# DC-DC_5V.net
KiCad netlist of a schematic drawn in EasyEDA Pro
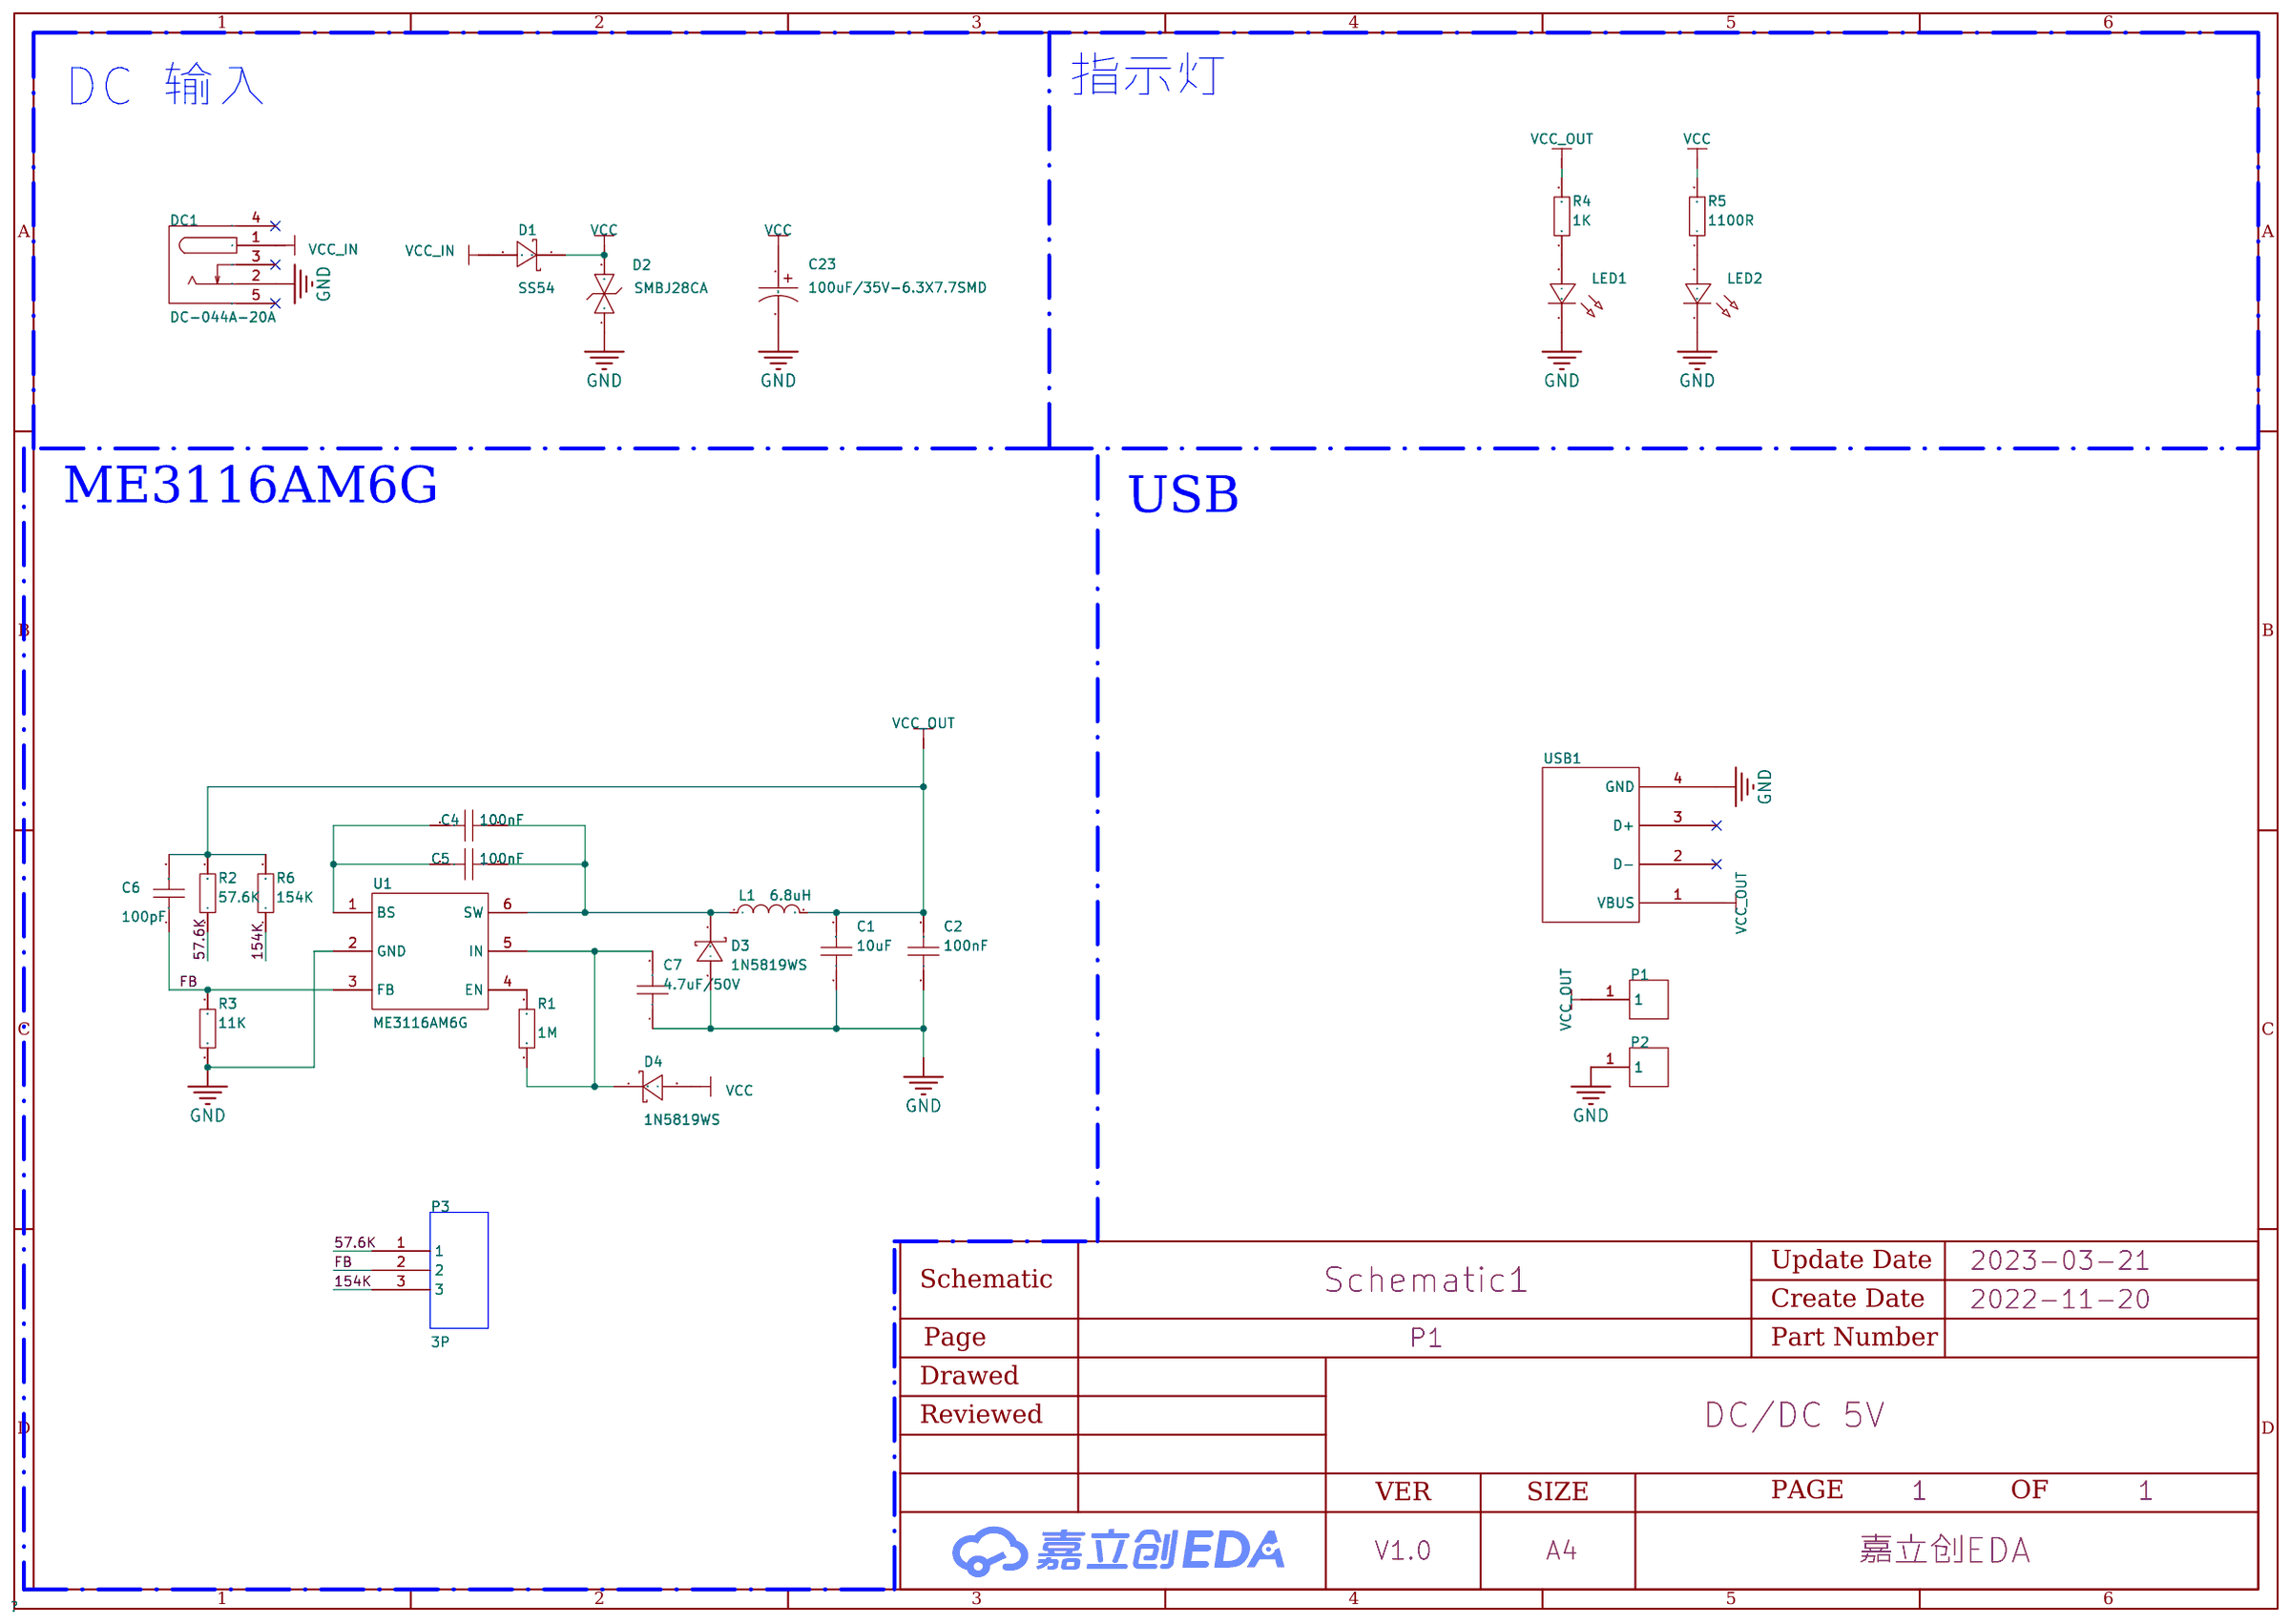
[diagram p0: schematic sheet]

(export (version "E")
  (design (tool "Eeschema 10.0.6"))
  (components
    (comp (ref "C1")
      (value "100nF")
      (footprint "easyedapro:C0603")
      (libsource (lib "easyedapro") (part "C1210X7R475K630NT"))
    )
    (comp (ref "C2")
      (value "100nF")
      (footprint "easyedapro:C0603")
      (libsource (lib "easyedapro") (part "C1210X7R475K630NT"))
    )
    (comp (ref "C4")
      (value "100nF")
      (footprint "easyedapro:C0603")
      (libsource (lib "easyedapro") (part "C1210X7R475K630NT"))
    )
    (comp (ref "C5")
      (value "100nF")
      (footprint "easyedapro:C0603")
      (libsource (lib "easyedapro") (part "C1210X7R475K630NT"))
    )
    (comp (ref "C6")
      (value "100nF")
      (footprint "easyedapro:C0603")
      (libsource (lib "easyedapro") (part "C1210X7R475K630NT"))
    )
    (comp (ref "C7")
      (value "100nF")
      (footprint "easyedapro:C0603")
      (libsource (lib "easyedapro") (part "C1210X7R475K630NT"))
    )
    (comp (ref "C23")
      (value "100uF/35V-6.3X7.7SMD")
      (footprint "easyedapro:CAP-SMD_BD6.3-L6.6-W6.6-FD")
      (libsource (lib "easyedapro") (part "100UF/35V-6.3X7.7SMD"))
    )
    (comp (ref "D1")
      (value "SS54")
      (footprint "easyedapro:SMA_L4.2-W2.6-LS5.3-RD")
      (fields (field (name "Manufacturer") "CJ(江苏长电/长晶)"))
      (libsource (lib "easyedapro") (part "SS54_C2929944"))
    )
    (comp (ref "D2")
      (value "SMBJ28CA")
      (footprint "easyedapro:SMB_L4.6-W3.6-LS5.3-BI")
      (description "极性:双向;")
      (fields (field (name "Manufacturer") "TWGMC(台湾迪嘉)"))
      (libsource (lib "easyedapro") (part "SMBJ28CA_C726872"))
    )
    (comp (ref "D3")
      (value "1N5819WS")
      (footprint "easyedapro:SOD-323_L1.8-W1.3-LS2.5-RD")
      (description "直流反向耐压(Vr):40V;平均整流电流(Io):1A;正向压降(Vf):900mV@3A;")
      (fields (field (name "Manufacturer") "PJSEMI(平晶微)"))
      (libsource (lib "easyedapro") (part "1N5819WS_C440261"))
    )
    (comp (ref "D4")
      (value "1N5819WS")
      (footprint "easyedapro:SOD-323_L1.8-W1.3-LS2.5-RD")
      (description "直流反向耐压(Vr):40V;平均整流电流(Io):1A;正向压降(Vf):900mV@3A;")
      (fields (field (name "Manufacturer") "PJSEMI(平晶微)"))
      (libsource (lib "easyedapro") (part "1N5819WS_C440261"))
    )
    (comp (ref "DC1")
      (value "DC-044A-20A")
      (footprint "easyedapro:DC-IN-TH_DC-044A-20A")
      (description "触点内径:2mm;触点外径:0.9mm;")
      (fields (field (name "Manufacturer") "韩国韩荣"))
      (libsource (lib "easyedapro") (part "DC-044A-20A"))
    )
    (comp (ref "L1")
      (value "10uH")
      (footprint "easyedapro:IND-SMD_L7.4-W6.6")
      (description "电感值:10uH;精度:±20%;额定电流:4A;饱和电流(Isat):5A;直流电阻(DCR):68mΩ;")
      (fields (field (name "Manufacturer Part") "CKST0603-10uH/M") (field (name "Manufacturer") "CENKER(岑科)"))
      (libsource (lib "easyedapro") (part "CKST0603-10UH/M"))
    )
    (comp (ref "LED1")
      (value "~")
      (footprint "easyedapro:LED0805-RD_RED")
      (libsource (lib "easyedapro") (part "LED_G"))
    )
    (comp (ref "LED2")
      (value "~")
      (footprint "easyedapro:LED0805-RD_RED")
      (libsource (lib "easyedapro") (part "LED_G"))
    )
    (comp (ref "P1") (value "~") (footprint "easyedapro:铜柱 M2") (libsource (lib "easyedapro") (part "铜柱 M2")))
    (comp (ref "P2") (value "~") (footprint "easyedapro:铜柱 M2") (libsource (lib "easyedapro") (part "铜柱 M2")))
    (comp (ref "P3")
      (value "3P")
      (footprint "easyedapro:Header-3P-2.54")
      (description "2.54mm 排针")
      (libsource (lib "easyedapro") (part "Header-3P-2.54"))
    )
    (comp (ref "R1") (value "10K") (footprint "easyedapro:R0603") (libsource (lib "easyedapro") (part "电阻")))
    (comp (ref "R2") (value "10K") (footprint "easyedapro:R0603") (libsource (lib "easyedapro") (part "电阻")))
    (comp (ref "R3") (value "10K") (footprint "easyedapro:R0603") (libsource (lib "easyedapro") (part "电阻")))
    (comp (ref "R4") (value "10K") (footprint "easyedapro:R0603") (libsource (lib "easyedapro") (part "电阻")))
    (comp (ref "R5") (value "10K") (footprint "easyedapro:R0603") (libsource (lib "easyedapro") (part "电阻")))
    (comp (ref "R6") (value "154K") (footprint "easyedapro:R0603") (libsource (lib "easyedapro") (part "电阻")))
    (comp (ref "U1")
      (value "ME3116AM6G")
      (footprint "easyedapro:SOT-23-6_L2.9-W1.6-P0.95-LS2.8-BR")
      (description "功能类型:降压型;同步整流:-;输出通道数:-;拓扑结构:-;输入电压:-;输出电流(最大值):-;开关频率:-;")
      (fields (field (name "Manufacturer") "MICRONE(南京微盟)"))
      (libsource (lib "easyedapro") (part "ME3116"))
    )
    (comp (ref "USB1")
      (value "~")
      (footprint "easyedapro:USB-A Short")
      (libsource (lib "easyedapro") (part "USB-A Short"))
    )
  )
  (nets
    (net (code "1") (name "/57.6K") (class "Default")
      (node (ref "P3") (pin "1") (pinfunction "1_1") (pintype "input"))
      (node (ref "R2") (pin "1") (pinfunction "1_1") (pintype "input"))
    )
    (net (code "2") (name "/154K") (class "Default")
      (node (ref "P3") (pin "3") (pinfunction "3_3") (pintype "input"))
      (node (ref "R6") (pin "1") (pinfunction "1_1") (pintype "input"))
    )
    (net (code "3") (name "/FB") (class "Default")
      (node (ref "C6") (pin "1") (pinfunction "1_1") (pintype "input"))
      (node (ref "P3") (pin "2") (pinfunction "2_2") (pintype "input"))
      (node (ref "R3") (pin "2") (pinfunction "2_2") (pintype "input"))
      (node (ref "U1") (pin "3") (pinfunction "FB_3") (pintype "input"))
    )
    (net (code "4") (name "GND") (class "Default")
      (node (ref "C1") (pin "1") (pinfunction "1_1") (pintype "input"))
      (node (ref "C2") (pin "1") (pinfunction "1_1") (pintype "input"))
      (node (ref "C23") (pin "2") (pinfunction "2_2") (pintype "input"))
      (node (ref "C7") (pin "1") (pinfunction "1_1") (pintype "input"))
      (node (ref "D2") (pin "1") (pinfunction "1_1") (pintype "input"))
      (node (ref "D3") (pin "2") (pinfunction "A_2") (pintype "input"))
      (node (ref "DC1") (pin "2") (pinfunction "2_2") (pintype "input"))
      (node (ref "LED1") (pin "1") (pinfunction "C_1") (pintype "input"))
      (node (ref "LED2") (pin "1") (pinfunction "C_1") (pintype "input"))
      (node (ref "P2") (pin "1") (pinfunction "1_1") (pintype "input"))
      (node (ref "R3") (pin "1") (pinfunction "1_1") (pintype "input"))
      (node (ref "U1") (pin "2") (pinfunction "GND_2") (pintype "input"))
      (node (ref "USB1") (pin "4") (pinfunction "GND_4") (pintype "input"))
    )
    (net (code "5") (name "Net-(D3-C)") (class "Default")
      (node (ref "C4") (pin "1") (pinfunction "1_1") (pintype "input"))
      (node (ref "C5") (pin "1") (pinfunction "1_1") (pintype "input"))
      (node (ref "D3") (pin "1") (pinfunction "C_1") (pintype "input"))
      (node (ref "L1") (pin "1") (pinfunction "1_1") (pintype "input"))
      (node (ref "U1") (pin "6") (pinfunction "SW_6") (pintype "input"))
    )
    (net (code "6") (name "Net-(D4-C)") (class "Default")
      (node (ref "C7") (pin "2") (pinfunction "2_2") (pintype "input"))
      (node (ref "D4") (pin "1") (pinfunction "C_1") (pintype "input"))
      (node (ref "R1") (pin "1") (pinfunction "1_1") (pintype "input"))
      (node (ref "U1") (pin "5") (pinfunction "IN_5") (pintype "input"))
    )
    (net (code "7") (name "Net-(LED1-A)") (class "Default")
      (node (ref "LED1") (pin "2") (pinfunction "A_2") (pintype "input"))
      (node (ref "R4") (pin "1") (pinfunction "1_1") (pintype "input"))
    )
    (net (code "8") (name "Net-(LED2-A)") (class "Default")
      (node (ref "LED2") (pin "2") (pinfunction "A_2") (pintype "input"))
      (node (ref "R5") (pin "1") (pinfunction "1_1") (pintype "input"))
    )
    (net (code "9") (name "Net-(U1-BS)") (class "Default")
      (node (ref "C4") (pin "2") (pinfunction "2_2") (pintype "input"))
      (node (ref "C5") (pin "2") (pinfunction "2_2") (pintype "input"))
      (node (ref "U1") (pin "1") (pinfunction "BS_1") (pintype "input"))
    )
    (net (code "10") (name "Net-(U1-EN)") (class "Default")
      (node (ref "R1") (pin "2") (pinfunction "2_2") (pintype "input"))
      (node (ref "U1") (pin "4") (pinfunction "EN_4") (pintype "input"))
    )
    (net (code "11") (name "VCC") (class "Default")
      (node (ref "C23") (pin "1") (pinfunction "1_1") (pintype "input"))
      (node (ref "D1") (pin "1") (pinfunction "C_1") (pintype "input"))
      (node (ref "D2") (pin "2") (pinfunction "2_2") (pintype "input"))
      (node (ref "D4") (pin "2") (pinfunction "A_2") (pintype "input"))
      (node (ref "R5") (pin "2") (pinfunction "2_2") (pintype "input"))
    )
    (net (code "12") (name "VCC_IN") (class "Default")
      (node (ref "D1") (pin "2") (pinfunction "A_2") (pintype "input"))
      (node (ref "DC1") (pin "1") (pinfunction "1_1") (pintype "input"))
    )
    (net (code "13") (name "VCC_OUT") (class "Default")
      (node (ref "C1") (pin "2") (pinfunction "2_2") (pintype "input"))
      (node (ref "C2") (pin "2") (pinfunction "2_2") (pintype "input"))
      (node (ref "C6") (pin "2") (pinfunction "2_2") (pintype "input"))
      (node (ref "L1") (pin "2") (pinfunction "2_2") (pintype "input"))
      (node (ref "P1") (pin "1") (pinfunction "1_1") (pintype "input"))
      (node (ref "R2") (pin "2") (pinfunction "2_2") (pintype "input"))
      (node (ref "R4") (pin "2") (pinfunction "2_2") (pintype "input"))
      (node (ref "R6") (pin "2") (pinfunction "2_2") (pintype "input"))
      (node (ref "USB1") (pin "1") (pinfunction "VBUS_1") (pintype "input"))
    )
    (net (code "14") (name "unconnected-(DC1-Pad3)") (class "Default")
      (node (ref "DC1") (pin "3") (pinfunction "3_3") (pintype "input+no_connect"))
    )
    (net (code "15") (name "unconnected-(DC1-Pad4)") (class "Default")
      (node (ref "DC1") (pin "4") (pinfunction "4_4") (pintype "input+no_connect"))
    )
    (net (code "16") (name "unconnected-(DC1-Pad5)") (class "Default")
      (node (ref "DC1") (pin "5") (pinfunction "5_5") (pintype "input+no_connect"))
    )
    (net (code "17") (name "unconnected-(USB1-D+-Pad3)") (class "Default")
      (node (ref "USB1") (pin "3") (pinfunction "D+_3") (pintype "input+no_connect"))
    )
    (net (code "18") (name "unconnected-(USB1-D--Pad2)") (class "Default")
      (node (ref "USB1") (pin "2") (pinfunction "D-_2") (pintype "input+no_connect"))
    )
  )
)
